# Pasa_Altos.net
KiCad netlist of a schematic drawn in Altium Designer
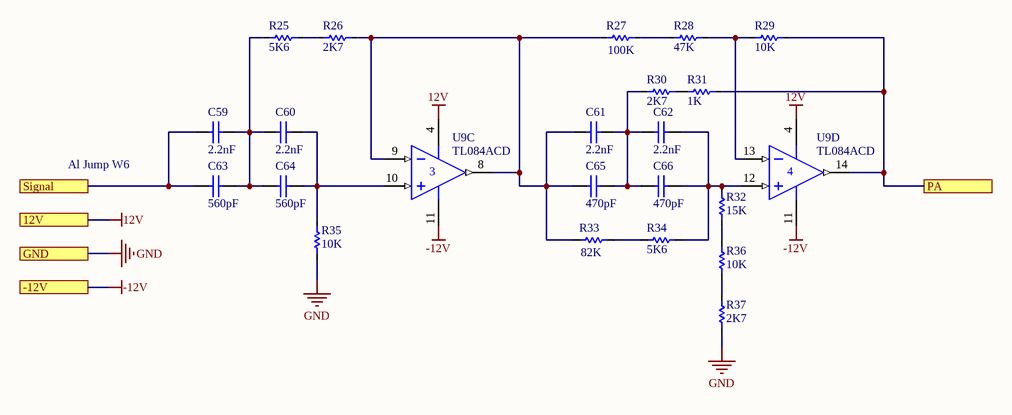
[diagram p0: Pasa Altos.SchDoc]

(export (version "E")
  (design (tool "Eeschema 10.0.6"))
  (components
    (comp (ref "C59")
      (value "Cap Ceramico Disco")
      (footprint "cap 10")
      (description "Capacitor Ceramico de Insercion")
      (fields (field (name "VALOR") "2.2nF"))
      (libsource (lib "RUF-Dispositivos-Grales") (part "Cap Ceramico Disco"))
    )
    (comp (ref "C60")
      (value "Cap Ceramico Disco")
      (footprint "cap 10")
      (description "Capacitor Ceramico de Insercion")
      (fields (field (name "VALOR") "2.2nF"))
      (libsource (lib "RUF-Dispositivos-Grales") (part "Cap Ceramico Disco"))
    )
    (comp (ref "C61")
      (value "Cap Ceramico Disco")
      (footprint "cap 10")
      (description "Capacitor Ceramico de Insercion")
      (fields (field (name "VALOR") "2.2nF"))
      (libsource (lib "RUF-Dispositivos-Grales") (part "Cap Ceramico Disco"))
    )
    (comp (ref "C62")
      (value "Cap Ceramico Disco")
      (footprint "cap 10")
      (description "Capacitor Ceramico de Insercion")
      (fields (field (name "VALOR") "2.2nF"))
      (libsource (lib "RUF-Dispositivos-Grales") (part "Cap Ceramico Disco"))
    )
    (comp (ref "C63")
      (value "Cap Ceramico Disco")
      (footprint "CAP DISCO 200mil")
      (description "Capacitor Ceramico de Insercion")
      (fields (field (name "VALOR") "560pF"))
      (libsource (lib "RUF-Dispositivos-Grales") (part "Cap Ceramico Disco"))
    )
    (comp (ref "C64")
      (value "Cap Ceramico Disco")
      (footprint "CAP DISCO 200mil")
      (description "Capacitor Ceramico de Insercion")
      (fields (field (name "VALOR") "560pF"))
      (libsource (lib "RUF-Dispositivos-Grales") (part "Cap Ceramico Disco"))
    )
    (comp (ref "C65")
      (value "Cap Ceramico Disco")
      (footprint "cap 10")
      (description "Capacitor Ceramico de Insercion")
      (fields (field (name "VALOR") "470pF"))
      (libsource (lib "RUF-Dispositivos-Grales") (part "Cap Ceramico Disco"))
    )
    (comp (ref "C66")
      (value "Cap Ceramico Disco")
      (footprint "cap 10")
      (description "Capacitor Ceramico de Insercion")
      (fields (field (name "VALOR") "470pF"))
      (libsource (lib "RUF-Dispositivos-Grales") (part "Cap Ceramico Disco"))
    )
    (comp (ref "R25")
      (value "Res SMD")
      (footprint "1206 resistor")
      (description "Res Smd")
      (fields (field (name "VALOR") "5K6"))
      (libsource (lib "RUF-Dispositivos-Grales") (part "Res SMD"))
    )
    (comp (ref "R26")
      (value "Res SMD")
      (footprint "1206 resistor")
      (description "Res Smd")
      (fields (field (name "VALOR") "2K7"))
      (libsource (lib "RUF-Dispositivos-Grales") (part "Res SMD"))
    )
    (comp (ref "R27")
      (value "Res SMD")
      (footprint "RES AXIAL 400mil")
      (description "Res Smd")
      (fields (field (name "VALOR") "100K"))
      (libsource (lib "RUF-Dispositivos-Grales") (part "Res SMD"))
    )
    (comp (ref "R28")
      (value "Res SMD")
      (footprint "1206 resistor")
      (description "Res Smd")
      (fields (field (name "VALOR") "47K"))
      (libsource (lib "RUF-Dispositivos-Grales") (part "Res SMD"))
    )
    (comp (ref "R29")
      (value "Res SMD")
      (footprint "1206 resistor")
      (description "Res Smd")
      (fields (field (name "VALOR") "10K"))
      (libsource (lib "RUF-Dispositivos-Grales") (part "Res SMD"))
    )
    (comp (ref "R30")
      (value "Res SMD")
      (footprint "1206 resistor")
      (description "Res Smd")
      (fields (field (name "VALOR") "2K7"))
      (libsource (lib "RUF-Dispositivos-Grales") (part "Res SMD"))
    )
    (comp (ref "R31")
      (value "Res SMD")
      (footprint "1206 resistor")
      (description "Res Smd")
      (fields (field (name "VALOR") "1K"))
      (libsource (lib "RUF-Dispositivos-Grales") (part "Res SMD"))
    )
    (comp (ref "R32")
      (value "Res SMD")
      (footprint "1206 resistor")
      (description "Res Smd")
      (fields (field (name "VALOR") "15K"))
      (libsource (lib "RUF-Dispositivos-Grales") (part "Res SMD"))
    )
    (comp (ref "R33")
      (value "Res SMD")
      (footprint "RES AXIAL 400mil")
      (description "Res Smd")
      (fields (field (name "VALOR") "82K"))
      (libsource (lib "RUF-Dispositivos-Grales") (part "Res SMD"))
    )
    (comp (ref "R34")
      (value "Res SMD")
      (footprint "1206 resistor")
      (description "Res Smd")
      (fields (field (name "VALOR") "5K6"))
      (libsource (lib "RUF-Dispositivos-Grales") (part "Res SMD"))
    )
    (comp (ref "R35")
      (value "Res SMD")
      (footprint "1206 resistor")
      (description "Res Smd")
      (fields (field (name "VALOR") "10K"))
      (libsource (lib "RUF-Dispositivos-Grales") (part "Res SMD"))
    )
    (comp (ref "R36")
      (value "Res SMD")
      (footprint "1206 resistor")
      (description "Res Smd")
      (fields (field (name "VALOR") "10K"))
      (libsource (lib "RUF-Dispositivos-Grales") (part "Res SMD"))
    )
    (comp (ref "R37")
      (value "Res SMD")
      (footprint "1206 resistor")
      (description "Res Smd")
      (fields (field (name "VALOR") "2K7"))
      (libsource (lib "RUF-Dispositivos-Grales") (part "Res SMD"))
    )
    (comp (ref "U9")
      (value "TL084ACD")
      (footprint "751A-02_N")
      (description "JFET-Input Operational Amplifier")
      (fields (field (name "PUBLISHER") "Altium Limited"))
      (libsource (lib "Motorola Amplifier Operational Amplifier") (part "TL084ACD"))
    )
  )
  (nets
    (net (code "1") (name "-12V") (class "Default")
      (node (ref "U9") (pin "11") (pinfunction "V-_11") (pintype "power_in"))
    )
    (net (code "2") (name "/PA") (class "Default")
      (node (ref "R29") (pin "1") (pinfunction "1_1") (pintype "passive"))
      (node (ref "R31") (pin "1") (pinfunction "1_1") (pintype "passive"))
      (node (ref "U9") (pin "14") (pinfunction "OUT_14") (pintype "output"))
    )
    (net (code "3") (name "/Signal") (class "Default")
      (node (ref "C59") (pin "2") (pinfunction "2_2") (pintype "passive"))
      (node (ref "C63") (pin "2") (pinfunction "2_2") (pintype "passive"))
    )
    (net (code "4") (name "12V") (class "Default")
      (node (ref "U9") (pin "4") (pinfunction "V+_4") (pintype "power_in"))
    )
    (net (code "5") (name "GND") (class "Default")
      (node (ref "R35") (pin "1") (pinfunction "1_1") (pintype "passive"))
      (node (ref "R37") (pin "2") (pinfunction "2_2") (pintype "passive"))
    )
    (net (code "6") (name "Net-(C59-Pad1)") (class "Default")
      (node (ref "C59") (pin "1") (pinfunction "1_1") (pintype "passive"))
      (node (ref "C60") (pin "2") (pinfunction "2_2") (pintype "passive"))
      (node (ref "C63") (pin "1") (pinfunction "1_1") (pintype "passive"))
      (node (ref "C64") (pin "2") (pinfunction "2_2") (pintype "passive"))
      (node (ref "R25") (pin "2") (pinfunction "2_2") (pintype "passive"))
    )
    (net (code "7") (name "Net-(C61-Pad1)") (class "Default")
      (node (ref "C61") (pin "1") (pinfunction "1_1") (pintype "passive"))
      (node (ref "C62") (pin "2") (pinfunction "2_2") (pintype "passive"))
      (node (ref "C65") (pin "1") (pinfunction "1_1") (pintype "passive"))
      (node (ref "C66") (pin "2") (pinfunction "2_2") (pintype "passive"))
      (node (ref "R30") (pin "2") (pinfunction "2_2") (pintype "passive"))
    )
    (net (code "8") (name "Net-(R25-Pad1)") (class "Default")
      (node (ref "R25") (pin "1") (pinfunction "1_1") (pintype "passive"))
      (node (ref "R26") (pin "2") (pinfunction "2_2") (pintype "passive"))
    )
    (net (code "9") (name "Net-(R27-Pad2)") (class "Default")
      (node (ref "R27") (pin "2") (pinfunction "2_2") (pintype "passive"))
      (node (ref "R28") (pin "2") (pinfunction "2_2") (pintype "passive"))
    )
    (net (code "10") (name "Net-(R30-Pad1)") (class "Default")
      (node (ref "R30") (pin "1") (pinfunction "1_1") (pintype "passive"))
      (node (ref "R31") (pin "2") (pinfunction "2_2") (pintype "passive"))
    )
    (net (code "11") (name "Net-(R32-Pad2)") (class "Default")
      (node (ref "R32") (pin "2") (pinfunction "2_2") (pintype "passive"))
      (node (ref "R36") (pin "1") (pinfunction "1_1") (pintype "passive"))
    )
    (net (code "12") (name "Net-(R33-Pad2)") (class "Default")
      (node (ref "R33") (pin "2") (pinfunction "2_2") (pintype "passive"))
      (node (ref "R34") (pin "2") (pinfunction "2_2") (pintype "passive"))
    )
    (net (code "13") (name "Net-(R36-Pad2)") (class "Default")
      (node (ref "R36") (pin "2") (pinfunction "2_2") (pintype "passive"))
      (node (ref "R37") (pin "1") (pinfunction "1_1") (pintype "passive"))
    )
    (net (code "14") (name "Net-(U9C-IN+)") (class "Default")
      (node (ref "C60") (pin "1") (pinfunction "1_1") (pintype "passive"))
      (node (ref "C64") (pin "1") (pinfunction "1_1") (pintype "passive"))
      (node (ref "R35") (pin "2") (pinfunction "2_2") (pintype "passive"))
      (node (ref "U9") (pin "10") (pinfunction "IN+_10") (pintype "input"))
    )
    (net (code "15") (name "Net-(U9C-IN-)") (class "Default")
      (node (ref "C61") (pin "2") (pinfunction "2_2") (pintype "passive"))
      (node (ref "C65") (pin "2") (pinfunction "2_2") (pintype "passive"))
      (node (ref "R26") (pin "1") (pinfunction "1_1") (pintype "passive"))
      (node (ref "R27") (pin "1") (pinfunction "1_1") (pintype "passive"))
      (node (ref "R33") (pin "1") (pinfunction "1_1") (pintype "passive"))
      (node (ref "U9") (pin "8") (pinfunction "OUT_8") (pintype "output"))
      (node (ref "U9") (pin "9") (pinfunction "IN-_9") (pintype "input"))
    )
    (net (code "16") (name "Net-(U9D-IN+)") (class "Default")
      (node (ref "C62") (pin "1") (pinfunction "1_1") (pintype "passive"))
      (node (ref "C66") (pin "1") (pinfunction "1_1") (pintype "passive"))
      (node (ref "R32") (pin "1") (pinfunction "1_1") (pintype "passive"))
      (node (ref "R34") (pin "1") (pinfunction "1_1") (pintype "passive"))
      (node (ref "U9") (pin "12") (pinfunction "IN+_12") (pintype "input"))
    )
    (net (code "17") (name "Net-(U9D-IN-)") (class "Default")
      (node (ref "R28") (pin "1") (pinfunction "1_1") (pintype "passive"))
      (node (ref "R29") (pin "2") (pinfunction "2_2") (pintype "passive"))
      (node (ref "U9") (pin "13") (pinfunction "IN-_13") (pintype "input"))
    )
  )
)
